# POWER.net
KiCad netlist of a schematic drawn in Altium Designer
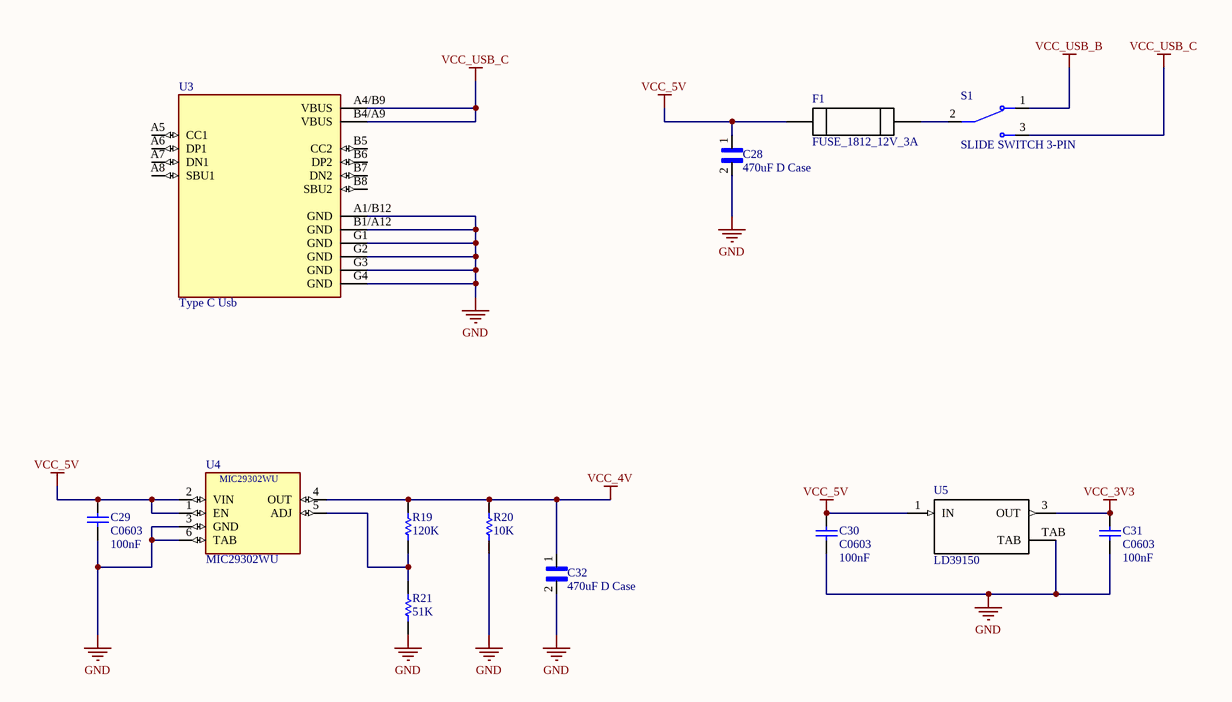
[diagram p0: POWER.SchDoc]

(export (version "E")
  (design (tool "Eeschema 10.0.6"))
  (components
    (comp (ref "C28")
      (value "470uF D Case")
      (footprint "470uF D Case")
      (libsource (lib "haberlesme") (part "470uF D Case"))
    )
    (comp (ref "C29")
      (value "C0603")
      (footprint "C0603")
      (description "Ceramic Chip Capacitor - Standard")
      (fields (field (name "ALTIUM_VALUE") "100nF") (field (name "PUBLISHER") "Altium Limited"))
      (libsource (lib "haberlesme") (part "C0603"))
    )
    (comp (ref "C30")
      (value "C0603")
      (footprint "C0603")
      (description "Ceramic Chip Capacitor - Standard")
      (fields (field (name "ALTIUM_VALUE") "100nF") (field (name "PUBLISHER") "Altium Limited"))
      (libsource (lib "haberlesme") (part "C0603"))
    )
    (comp (ref "C31")
      (value "C0603")
      (footprint "C0603")
      (description "Ceramic Chip Capacitor - Standard")
      (fields (field (name "ALTIUM_VALUE") "100nF") (field (name "PUBLISHER") "Altium Limited"))
      (libsource (lib "haberlesme") (part "C0603"))
    )
    (comp (ref "C32")
      (value "470uF D Case")
      (footprint "470uF D Case")
      (libsource (lib "haberlesme") (part "470uF D Case"))
    )
    (comp (ref "F1")
      (value "FUSE_1812_12V_3A")
      (footprint "FUSE_1812_12V_3A")
      (libsource (lib "haberlesme") (part "FUSE_1812_12V_3A"))
    )
    (comp (ref "R19")
      (value "120K")
      (footprint "Isbak:CC1608-0603")
      (description "Resistor")
      (fields
        (field (name "MANUFACTURER") "Generic Components")
        (field (name "Comment") "Res0603")
        (field (name "PUBLISHER") "Altium Limited")
      )
      (libsource (lib "Isbak") (part "Res0603"))
    )
    (comp (ref "R20")
      (value "10K")
      (footprint "Isbak:CC1608-0603")
      (description "Resistor")
      (fields
        (field (name "MANUFACTURER") "Generic Components")
        (field (name "Comment") "Res0603")
        (field (name "PUBLISHER") "Altium Limited")
      )
      (libsource (lib "Isbak") (part "Res0603"))
    )
    (comp (ref "R21")
      (value "51K")
      (footprint "Isbak:CC1608-0603")
      (description "Resistor")
      (fields
        (field (name "MANUFACTURER") "Generic Components")
        (field (name "Comment") "Res0603")
        (field (name "PUBLISHER") "Altium Limited")
      )
      (libsource (lib "Isbak") (part "Res0603"))
    )
    (comp (ref "S1")
      (value "SLIDE SWITCH 3-PIN")
      (footprint "Slide Switch 3-Pin")
      (libsource (lib "haberlesme") (part "SLIDE SWITCH 3-PIN"))
    )
    (comp (ref "U3")
      (value "Type C Usb")
      (footprint "Type C Usb")
      (libsource (lib "haberlesme") (part "Type C Usb"))
    )
    (comp (ref "U4")
      (value "MIC29302WU")
      (footprint "MIC29302WU")
      (libsource (lib "haberlesme") (part "MIC29302WU"))
    )
    (comp (ref "U5")
      (value "LD39150")
      (footprint "LD39150DT33-R")
      (libsource (lib "haberlesme") (part "LD39150"))
    )
  )
  (nets
    (net (code "1") (name "GND") (class "Default")
      (node (ref "C28") (pin "2") (pinfunction "2_2") (pintype "passive"))
      (node (ref "C29") (pin "1") (pinfunction "1_1") (pintype "passive"))
      (node (ref "C30") (pin "1") (pinfunction "1_1") (pintype "passive"))
      (node (ref "C31") (pin "1") (pinfunction "1_1") (pintype "passive"))
      (node (ref "C32") (pin "2") (pinfunction "2_2") (pintype "passive"))
      (node (ref "R20") (pin "2") (pinfunction "2_2") (pintype "passive"))
      (node (ref "R21") (pin "2") (pinfunction "2_2") (pintype "passive"))
      (node (ref "U3") (pin "A1/B12") (pinfunction "GND_A1/B12") (pintype "power_in"))
      (node (ref "U3") (pin "B1/A12") (pinfunction "GND_B1/A12") (pintype "power_in"))
      (node (ref "U3") (pin "G1") (pinfunction "GND_G1") (pintype "power_in"))
      (node (ref "U3") (pin "G2") (pinfunction "GND_G2") (pintype "power_in"))
      (node (ref "U3") (pin "G3") (pinfunction "GND_G3") (pintype "power_in"))
      (node (ref "U3") (pin "G4") (pinfunction "GND_G4") (pintype "power_in"))
      (node (ref "U4") (pin "3") (pinfunction "GND_3") (pintype "bidirectional"))
      (node (ref "U4") (pin "6") (pinfunction "TAB_6") (pintype "bidirectional"))
      (node (ref "U5") (pin "TAB") (pinfunction "TAB_TAB") (pintype "power_in"))
    )
    (net (code "2") (name "Net-(F1-Pad2)") (class "Default")
      (node (ref "F1") (pin "2") (pinfunction "2_2") (pintype "passive"))
      (node (ref "S1") (pin "2") (pinfunction "2_2") (pintype "passive"))
    )
    (net (code "3") (name "Net-(U4-ADJ)") (class "Default")
      (node (ref "R19") (pin "2") (pinfunction "2_2") (pintype "passive"))
      (node (ref "R21") (pin "1") (pinfunction "1_1") (pintype "passive"))
      (node (ref "U4") (pin "5") (pinfunction "ADJ_5") (pintype "bidirectional"))
    )
    (net (code "4") (name "VCC_3V3") (class "Default")
      (node (ref "C31") (pin "2") (pinfunction "2_2") (pintype "passive"))
      (node (ref "U5") (pin "3") (pinfunction "OUT_3") (pintype "output"))
    )
    (net (code "5") (name "VCC_4V") (class "Default")
      (node (ref "C32") (pin "1") (pinfunction "1_1") (pintype "passive"))
      (node (ref "R19") (pin "1") (pinfunction "1_1") (pintype "passive"))
      (node (ref "R20") (pin "1") (pinfunction "1_1") (pintype "passive"))
      (node (ref "U4") (pin "4") (pinfunction "OUT_4") (pintype "bidirectional"))
    )
    (net (code "6") (name "VCC_5V") (class "Default")
      (node (ref "C28") (pin "1") (pinfunction "1_1") (pintype "passive"))
      (node (ref "C29") (pin "2") (pinfunction "2_2") (pintype "passive"))
      (node (ref "C30") (pin "2") (pinfunction "2_2") (pintype "passive"))
      (node (ref "F1") (pin "1") (pinfunction "1_1") (pintype "passive"))
      (node (ref "U4") (pin "1") (pinfunction "EN_1") (pintype "bidirectional"))
      (node (ref "U4") (pin "2") (pinfunction "VIN_2") (pintype "bidirectional"))
      (node (ref "U5") (pin "1") (pinfunction "IN_1") (pintype "input"))
    )
    (net (code "7") (name "VCC_USB_B") (class "Default")
      (node (ref "S1") (pin "1") (pinfunction "1_1") (pintype "passive"))
    )
    (net (code "8") (name "VCC_USB_C") (class "Default")
      (node (ref "S1") (pin "3") (pinfunction "3_3") (pintype "passive"))
      (node (ref "U3") (pin "A4/B9") (pinfunction "VBUS_A4/B9") (pintype "power_in"))
      (node (ref "U3") (pin "B4/A9") (pinfunction "VBUS_B4/A9") (pintype "power_in"))
    )
    (net (code "9") (name "unconnected-(U3-CC1-PadA5)") (class "Default")
      (node (ref "U3") (pin "A5") (pinfunction "CC1_A5") (pintype "bidirectional"))
    )
    (net (code "10") (name "unconnected-(U3-CC2-PadB5)") (class "Default")
      (node (ref "U3") (pin "B5") (pinfunction "CC2_B5") (pintype "bidirectional"))
    )
    (net (code "11") (name "unconnected-(U3-DN1-PadA7)") (class "Default")
      (node (ref "U3") (pin "A7") (pinfunction "DN1_A7") (pintype "bidirectional"))
    )
    (net (code "12") (name "unconnected-(U3-DN2-PadB7)") (class "Default")
      (node (ref "U3") (pin "B7") (pinfunction "DN2_B7") (pintype "bidirectional"))
    )
    (net (code "13") (name "unconnected-(U3-DP1-PadA6)") (class "Default")
      (node (ref "U3") (pin "A6") (pinfunction "DP1_A6") (pintype "bidirectional"))
    )
    (net (code "14") (name "unconnected-(U3-DP2-PadB6)") (class "Default")
      (node (ref "U3") (pin "B6") (pinfunction "DP2_B6") (pintype "bidirectional"))
    )
    (net (code "15") (name "unconnected-(U3-SBU1-PadA8)") (class "Default")
      (node (ref "U3") (pin "A8") (pinfunction "SBU1_A8") (pintype "bidirectional"))
    )
    (net (code "16") (name "unconnected-(U3-SBU2-PadB8)") (class "Default")
      (node (ref "U3") (pin "B8") (pinfunction "SBU2_B8") (pintype "bidirectional"))
    )
  )
)
